# Power_Supply_Current_Transformers.net
KiCad netlist of a schematic drawn in Altium Designer
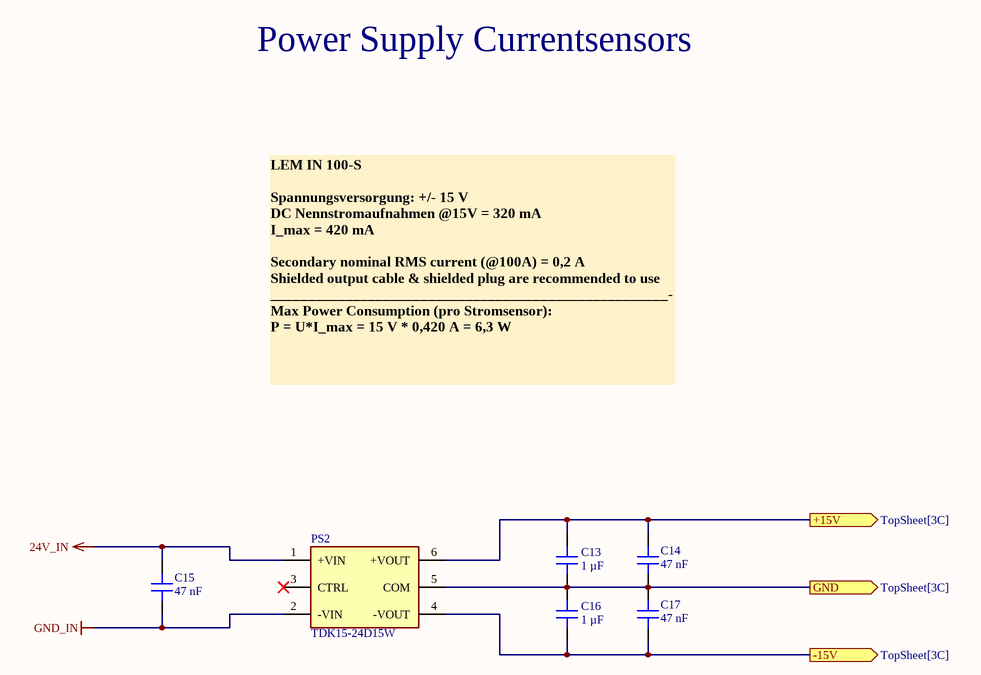
[diagram p0: Power_Supply_Current_Transformers.SchDoc]

(export (version "E")
  (design (tool "Eeschema 10.0.6"))
  (components
    (comp (ref "C13")
      (value "1 µF")
      (footprint "C_0603")
      (description "50V 1uF X5R ±10% 0603  Multilayer Ceramic Capacitors MLCC - SMD/SMT ROHS")
      (fields
        (field (name "MANUFACTURER") "Samsung Electro-Mechanics")
        (field (name "MANUFACTURER PART NUMBER") "CL10A105KB8NNNC")
        (field (name "CREATED FROM") "MGremer")
      )
      (libsource (lib "user") (part "Capacitor"))
    )
    (comp (ref "C14")
      (value "47 nF")
      (footprint "C_0603")
      (description "Capacitor 0603, 50 VDC, 47 nF, X7R")
      (fields
        (field (name "MANUFACTURER PART NUMBER") "CL10B473KB8NNNC")
        (field (name "MANUFACTURER") "Samsung Electro-Mechanics")
        (field (name "CREATED FROM") "DHufnagel")
      )
      (libsource (lib "user") (part "Capacitor"))
    )
    (comp (ref "C15")
      (value "47 nF")
      (footprint "C_0603")
      (description "Capacitor 0603, 50 VDC, 47 nF, X7R")
      (fields
        (field (name "MANUFACTURER PART NUMBER") "CL10B473KB8NNNC")
        (field (name "MANUFACTURER") "Samsung Electro-Mechanics")
        (field (name "CREATED FROM") "DHufnagel")
      )
      (libsource (lib "user") (part "Capacitor"))
    )
    (comp (ref "C16")
      (value "1 µF")
      (footprint "C_0603")
      (description "50V 1uF X5R ±10% 0603  Multilayer Ceramic Capacitors MLCC - SMD/SMT ROHS")
      (fields
        (field (name "MANUFACTURER") "Samsung Electro-Mechanics")
        (field (name "MANUFACTURER PART NUMBER") "CL10A105KB8NNNC")
        (field (name "CREATED FROM") "MGremer")
      )
      (libsource (lib "user") (part "Capacitor"))
    )
    (comp (ref "C17")
      (value "47 nF")
      (footprint "C_0603")
      (description "Capacitor 0603, 50 VDC, 47 nF, X7R")
      (fields
        (field (name "MANUFACTURER PART NUMBER") "CL10B473KB8NNNC")
        (field (name "MANUFACTURER") "Samsung Electro-Mechanics")
        (field (name "CREATED FROM") "DHufnagel")
      )
      (libsource (lib "user") (part "Capacitor"))
    )
    (comp (ref "PS2")
      (value "TDK15-24D15W")
      (footprint "TDK15-24D15W")
      (description "Isolated Module DC DC Converter Buck 2 Output ±15V 500mA 9V~36V Input")
      (fields
        (field (name "MANUFACTURER") "TDPOWER")
        (field (name "LCSC PART NUMBER") "C783530")
        (field (name "CREATED FROM") "TGaupp")
      )
      (libsource (lib "user") (part "TDK15-24D15W"))
    )
  )
  (nets
    (net (code "1") (name "/+15V") (class "Default")
      (node (ref "C13") (pin "2") (pinfunction "2_2") (pintype "passive"))
      (node (ref "C14") (pin "2") (pinfunction "2_2") (pintype "passive"))
      (node (ref "PS2") (pin "6") (pinfunction "+VOUT_6") (pintype "power_in"))
    )
    (net (code "2") (name "/-15V") (class "Default")
      (node (ref "C16") (pin "1") (pinfunction "1_1") (pintype "passive"))
      (node (ref "C17") (pin "1") (pinfunction "1_1") (pintype "passive"))
      (node (ref "PS2") (pin "4") (pinfunction "-VOUT_4") (pintype "power_in"))
    )
    (net (code "3") (name "/GND") (class "Default")
      (node (ref "C13") (pin "1") (pinfunction "1_1") (pintype "passive"))
      (node (ref "C14") (pin "1") (pinfunction "1_1") (pintype "passive"))
      (node (ref "C16") (pin "2") (pinfunction "2_2") (pintype "passive"))
      (node (ref "C17") (pin "2") (pinfunction "2_2") (pintype "passive"))
      (node (ref "PS2") (pin "5") (pinfunction "COM_5") (pintype "passive"))
    )
    (net (code "4") (name "24V_IN") (class "Default")
      (node (ref "C15") (pin "2") (pinfunction "2_2") (pintype "passive"))
      (node (ref "PS2") (pin "1") (pinfunction "+VIN_1") (pintype "power_in"))
    )
    (net (code "5") (name "GND_IN") (class "Default")
      (node (ref "C15") (pin "1") (pinfunction "1_1") (pintype "passive"))
      (node (ref "PS2") (pin "2") (pinfunction "-VIN_2") (pintype "power_in"))
    )
    (net (code "6") (name "unconnected-(PS2-CTRL-Pad3)") (class "Default")
      (node (ref "PS2") (pin "3") (pinfunction "CTRL_3") (pintype "passive+no_connect"))
    )
  )
)
